# Motor_Board.net
KiCad netlist of a schematic drawn in Altium Designer
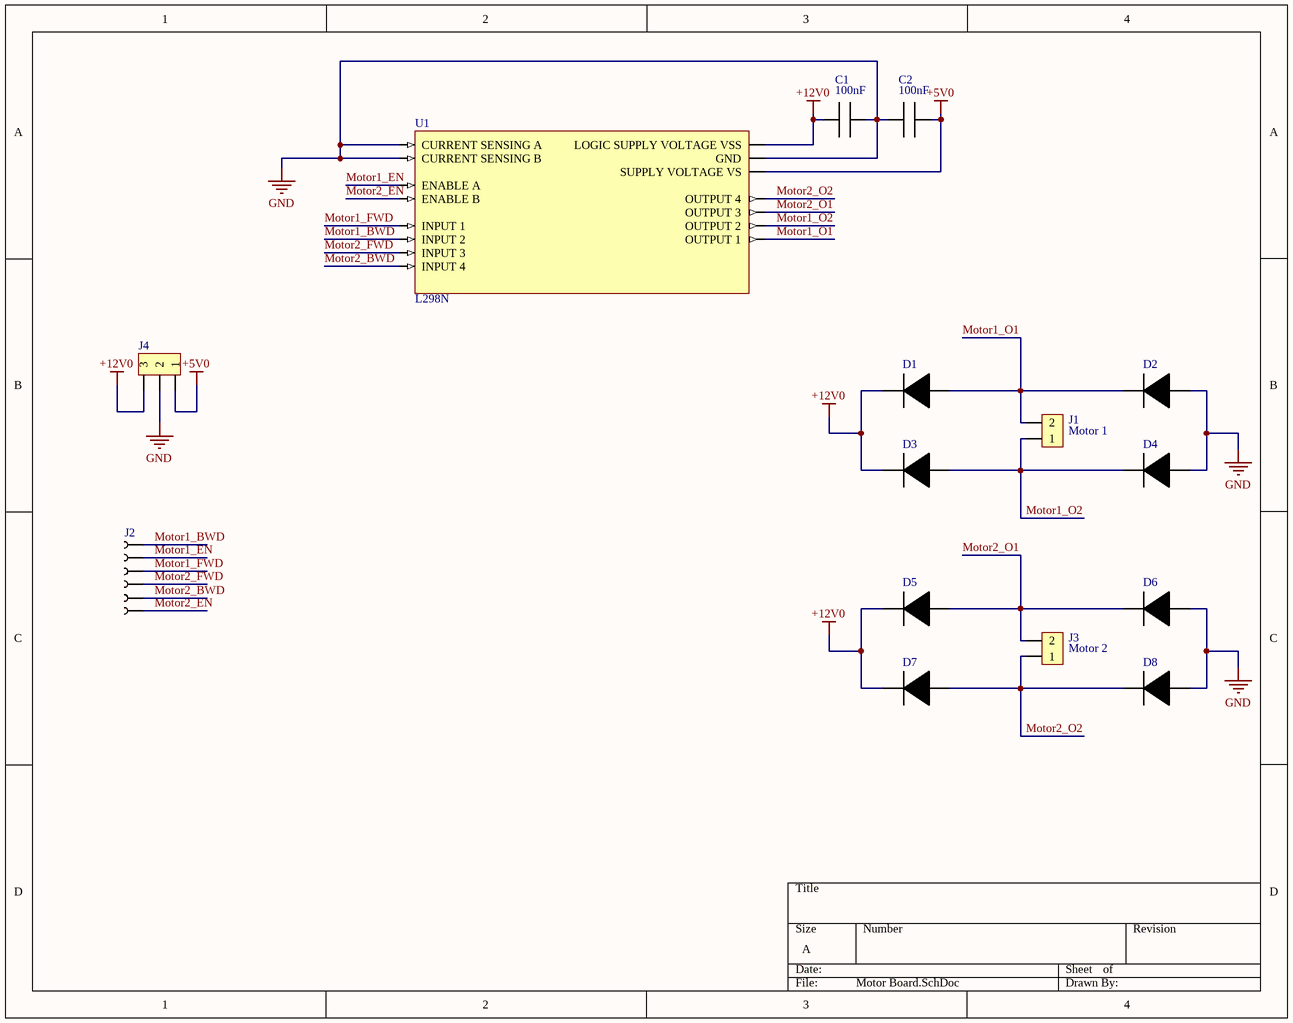
[diagram p0: Motor Board.SchDoc]

(export (version "E")
  (design (tool "Eeschema 10.0.6"))
  (components
    (comp (ref "C1")
      (value "100nF")
      (footprint "Ceramic Cap")
      (fields (field (name "Comment") "Ceramic Capacitor"))
      (libsource (lib "Components") (part "Ceramic Capacitor"))
    )
    (comp (ref "C2")
      (value "100nF")
      (footprint "Ceramic Cap")
      (fields (field (name "Comment") "Ceramic Capacitor"))
      (libsource (lib "Components") (part "Ceramic Capacitor"))
    )
    (comp (ref "D1") (value "Diode") (footprint "2A07") (libsource (lib "Components") (part "Diode")))
    (comp (ref "D2") (value "Diode") (footprint "2A07") (libsource (lib "Components") (part "Diode")))
    (comp (ref "D3") (value "Diode") (footprint "2A07") (libsource (lib "Components") (part "Diode")))
    (comp (ref "D4") (value "Diode") (footprint "2A07") (libsource (lib "Components") (part "Diode")))
    (comp (ref "D5") (value "Diode") (footprint "2A07") (libsource (lib "Components") (part "Diode")))
    (comp (ref "D6") (value "Diode") (footprint "2A07") (libsource (lib "Components") (part "Diode")))
    (comp (ref "D7") (value "Diode") (footprint "2A07") (libsource (lib "Components") (part "Diode")))
    (comp (ref "D8") (value "Diode") (footprint "2A07") (libsource (lib "Components") (part "Diode")))
    (comp (ref "J1")
      (value "Motor 1")
      (footprint "Terminal Block 2-pins")
      (fields (field (name "MF") "Phoenix Contact"))
      (libsource (lib "Components") (part "Terminal Block 2-pins"))
    )
    (comp (ref "J2")
      (value "Headers-6")
      (footprint "Headers 6-pins")
      (libsource (lib "Components") (part "Headers-6"))
    )
    (comp (ref "J3")
      (value "Motor 2")
      (footprint "Terminal Block 2-pins")
      (fields (field (name "MF") "Phoenix Contact"))
      (libsource (lib "Components") (part "Terminal Block 2-pins"))
    )
    (comp (ref "J4")
      (value "Terminal Block 3")
      (footprint "Terminal Block 3")
      (libsource (lib "Components") (part "Terminal Block 3"))
    )
    (comp (ref "U1") (value "L298N") (footprint "L298N") (libsource (lib "Components") (part "L298N")))
  )
  (nets
    (net (code "1") (name "+5V0") (class "Default")
      (node (ref "C2") (pin "2") (pintype "passive"))
      (node (ref "J4") (pin "1") (pinfunction "1_1") (pintype "passive"))
      (node (ref "U1") (pin "4") (pinfunction "SUPPLY_VOLTAGE_VS_4") (pintype "power_in"))
    )
    (net (code "2") (name "+12V0") (class "Default")
      (node (ref "C1") (pin "1") (pintype "passive"))
      (node (ref "D1") (pin "2") (pintype "passive"))
      (node (ref "D3") (pin "2") (pintype "passive"))
      (node (ref "D5") (pin "2") (pintype "passive"))
      (node (ref "D7") (pin "2") (pintype "passive"))
      (node (ref "J4") (pin "3") (pinfunction "3_3") (pintype "passive"))
      (node (ref "U1") (pin "9") (pinfunction "LOGIC_SUPPLY_VOLTAGE_VSS_9") (pintype "power_in"))
    )
    (net (code "3") (name "/Motor1_BWD") (class "Default")
      (node (ref "J2") (pin "1") (pintype "passive"))
      (node (ref "U1") (pin "7") (pinfunction "INPUT_2_7") (pintype "input"))
    )
    (net (code "4") (name "/Motor1_EN") (class "Default")
      (node (ref "J2") (pin "2") (pintype "passive"))
      (node (ref "U1") (pin "6") (pinfunction "ENABLE_A_6") (pintype "input"))
    )
    (net (code "5") (name "/Motor1_FWD") (class "Default")
      (node (ref "J2") (pin "3") (pintype "passive"))
      (node (ref "U1") (pin "5") (pinfunction "INPUT_1_5") (pintype "input"))
    )
    (net (code "6") (name "/Motor1_O1") (class "Default")
      (node (ref "D1") (pin "1") (pintype "passive"))
      (node (ref "D2") (pin "2") (pintype "passive"))
      (node (ref "J1") (pin "2") (pinfunction "2_2") (pintype "passive"))
      (node (ref "U1") (pin "2") (pinfunction "OUTPUT_1_2") (pintype "output"))
    )
    (net (code "7") (name "/Motor1_O2") (class "Default")
      (node (ref "D3") (pin "1") (pintype "passive"))
      (node (ref "D4") (pin "2") (pintype "passive"))
      (node (ref "J1") (pin "1") (pinfunction "1_1") (pintype "passive"))
      (node (ref "U1") (pin "3") (pinfunction "OUTPUT_2_3") (pintype "output"))
    )
    (net (code "8") (name "/Motor2_BWD") (class "Default")
      (node (ref "J2") (pin "5") (pintype "passive"))
      (node (ref "U1") (pin "12") (pinfunction "INPUT_4_12") (pintype "input"))
    )
    (net (code "9") (name "/Motor2_EN") (class "Default")
      (node (ref "J2") (pin "6") (pintype "passive"))
      (node (ref "U1") (pin "11") (pinfunction "ENABLE_B_11") (pintype "input"))
    )
    (net (code "10") (name "/Motor2_FWD") (class "Default")
      (node (ref "J2") (pin "4") (pintype "passive"))
      (node (ref "U1") (pin "10") (pinfunction "INPUT_3_10") (pintype "input"))
    )
    (net (code "11") (name "/Motor2_O1") (class "Default")
      (node (ref "D5") (pin "1") (pintype "passive"))
      (node (ref "D6") (pin "2") (pintype "passive"))
      (node (ref "J3") (pin "2") (pinfunction "2_2") (pintype "passive"))
      (node (ref "U1") (pin "13") (pinfunction "OUTPUT_3_13") (pintype "output"))
    )
    (net (code "12") (name "/Motor2_O2") (class "Default")
      (node (ref "D7") (pin "1") (pintype "passive"))
      (node (ref "D8") (pin "2") (pintype "passive"))
      (node (ref "J3") (pin "1") (pinfunction "1_1") (pintype "passive"))
      (node (ref "U1") (pin "14") (pinfunction "OUTPUT_4_14") (pintype "output"))
    )
    (net (code "13") (name "GND") (class "Default")
      (node (ref "C1") (pin "2") (pintype "passive"))
      (node (ref "C2") (pin "1") (pintype "passive"))
      (node (ref "D2") (pin "1") (pintype "passive"))
      (node (ref "D4") (pin "1") (pintype "passive"))
      (node (ref "D6") (pin "1") (pintype "passive"))
      (node (ref "D8") (pin "1") (pintype "passive"))
      (node (ref "J4") (pin "2") (pinfunction "2_2") (pintype "passive"))
      (node (ref "U1") (pin "1") (pinfunction "CURRENT_SENSING_A_1") (pintype "input"))
      (node (ref "U1") (pin "15") (pinfunction "CURRENT_SENSING_B_15") (pintype "input"))
      (node (ref "U1") (pin "8") (pinfunction "GND_8") (pintype "power_in"))
    )
  )
)
